# ZUM_Core.net
KiCad netlist of a schematic drawn in Altium Designer
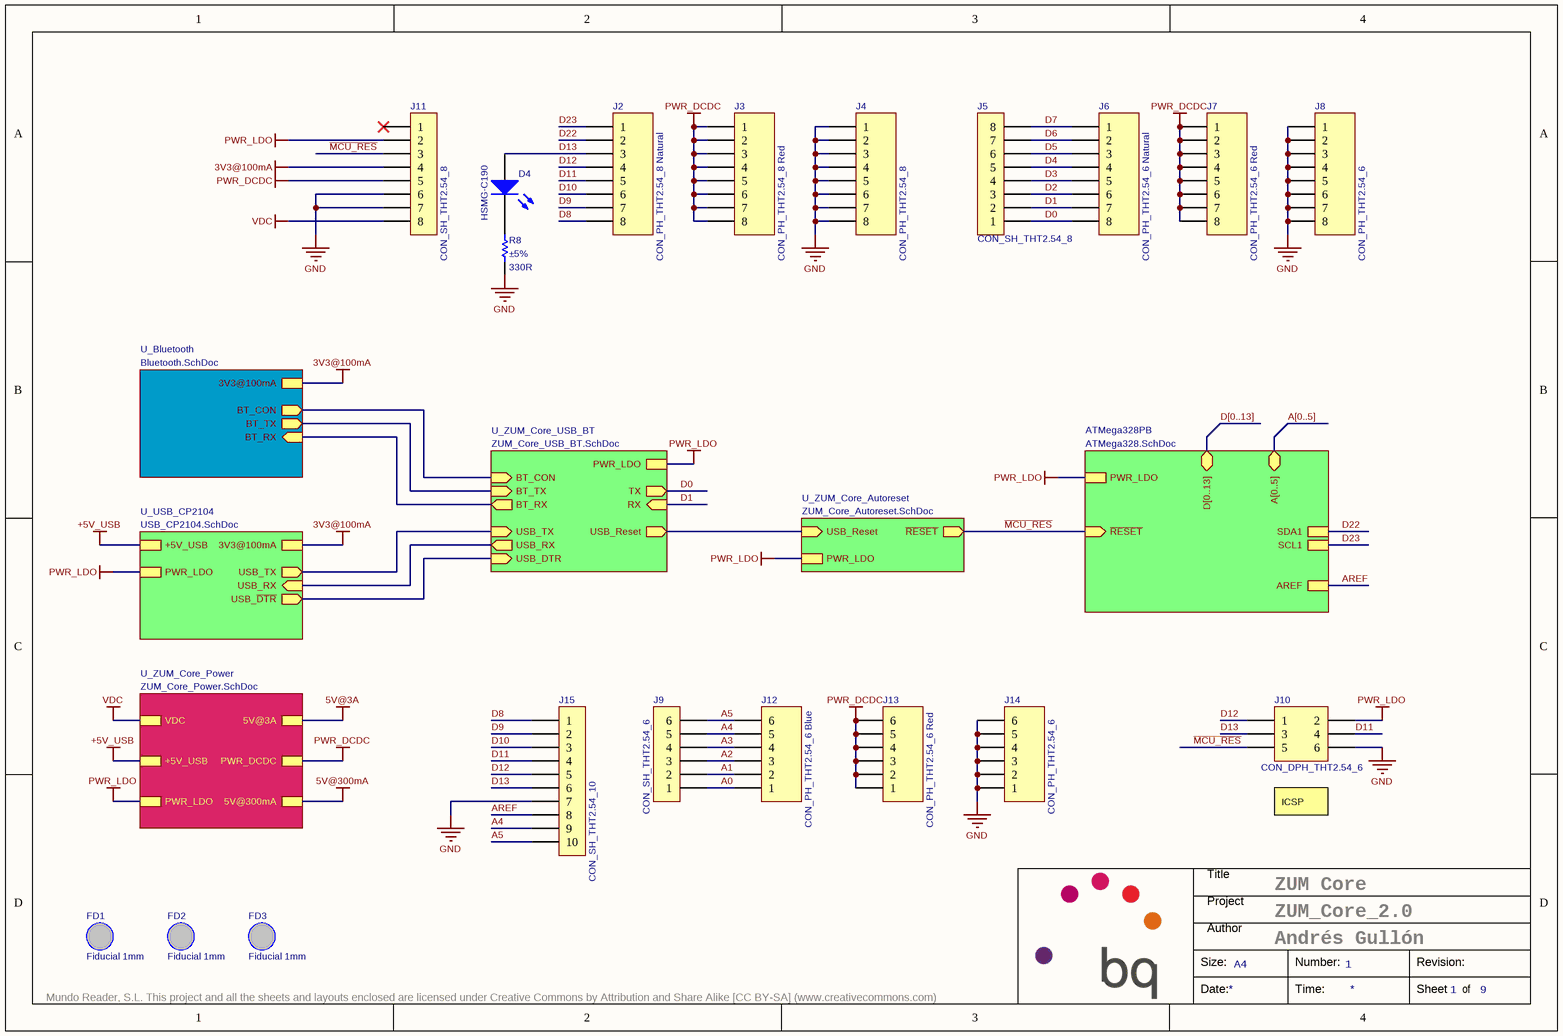
[diagram p0: ZUM_Core.SchDoc]

(export (version "E")
  (design (tool "Eeschema 10.0.6"))
  (components
    (comp (ref "D4")
      (value "HSMG-C190")
      (footprint "LED0603")
      (description "LED")
      (fields (field (name "MANUFACTURER") "Avago Technologies"))
      (libsource (lib "BQ Vault") (part "LED"))
    )
    (comp (ref "FD1")
      (value "Fiducial 1mm")
      (footprint "Fiducial_1mm")
      (description "Fiducial")
      (libsource (lib "BQ Vault") (part "Fiducial"))
    )
    (comp (ref "FD2")
      (value "Fiducial 1mm")
      (footprint "Fiducial_1mm")
      (description "Fiducial")
      (libsource (lib "BQ Vault") (part "Fiducial"))
    )
    (comp (ref "FD3")
      (value "Fiducial 1mm")
      (footprint "Fiducial_1mm")
      (description "Fiducial")
      (libsource (lib "BQ Vault") (part "Fiducial"))
    )
    (comp (ref "J2")
      (value "CON_PH_THT2.54_8 Natural")
      (footprint "1x8 Pin Header 2.54")
      (description "Connector")
      (fields (field (name "MANUFACTURER") "Samtec"))
      (libsource (lib "BQ Vault") (part "CMP-A2144-1"))
    )
    (comp (ref "J3")
      (value "CON_PH_THT2.54_8 Red")
      (footprint "1x8 Pin Header 2.54")
      (description "Connector")
      (fields (field (name "MANUFACTURER") "Samtec"))
      (libsource (lib "BQ Vault") (part "CMP-A2145-1"))
    )
    (comp (ref "J4")
      (value "CON_PH_THT2.54_8")
      (footprint "1x8 Pin Header 2.54")
      (description "Connector")
      (fields (field (name "MANUFACTURER") "Samtec"))
      (libsource (lib "BQ Vault") (part "CMP-A2142-1"))
    )
    (comp (ref "J5")
      (value "CON_SH_THT2.54_8")
      (footprint "1x8 Socket Header THT 2.54mm")
      (description "Connector")
      (fields (field (name "MANUFACTURER") "Samtec"))
      (libsource (lib "BQ Vault") (part "1x8 Socket Header 2.54mm"))
    )
    (comp (ref "J6")
      (value "CON_PH_THT2.54_6 Natural")
      (footprint "1x8 Header 2.54 (3D Mod)")
      (description "Connector")
      (fields (field (name "MANUFACTURER") "Samtec"))
      (libsource (lib "BQ Vault") (part "CMP-00382-1"))
    )
    (comp (ref "J7")
      (value "CON_PH_THT2.54_6 Red")
      (footprint "1x8 Header 2.54 (3D Mod)")
      (description "Connector")
      (fields (field (name "MANUFACTURER") "Samtec"))
      (libsource (lib "BQ Vault") (part "CMP-00380-2"))
    )
    (comp (ref "J8")
      (value "CON_PH_THT2.54_6")
      (footprint "1x8 Header 2.54 (3D Mod)")
      (description "Connector")
      (fields (field (name "MANUFACTURER") "Samtec"))
      (libsource (lib "BQ Vault") (part "1x8 pin Header 2.54mm"))
    )
    (comp (ref "J9")
      (value "CON_SH_THT2.54_6")
      (footprint "1x6 Socket Header THT 2.54mm")
      (description "Connector")
      (fields (field (name "MANUFACTURER") "Samtec"))
      (libsource (lib "BQ Vault") (part "1x6 Socket Header 2.54mm"))
    )
    (comp (ref "J10")
      (value "CON_DPH_THT2.54_6")
      (footprint "2x3 Pin Header 2.54")
      (description "Connector")
      (fields (field (name "MANUFACTURER") "Samtec"))
      (libsource (lib "BQ Vault") (part "CMP-A2163-1"))
    )
    (comp (ref "J11")
      (value "CON_SH_THT2.54_8")
      (footprint "1x8 Socket Header THT 2.54mm")
      (description "Connector")
      (fields (field (name "MANUFACTURER") "Samtec"))
      (libsource (lib "") (part "1x8 Socket Header 2.54mm_1"))
    )
    (comp (ref "J12")
      (value "CON_PH_THT2.54_6 Blue")
      (footprint "1x6 Pin Header 2.54")
      (description "Connector")
      (fields (field (name "MANUFACTURER") "Samtec"))
      (libsource (lib "BQ Vault") (part "CMP-A2139-1"))
    )
    (comp (ref "J13")
      (value "CON_PH_THT2.54_6 Red")
      (footprint "1x6 Pin Header 2.54")
      (description "Connector")
      (fields (field (name "MANUFACTURER") "Samtec"))
      (libsource (lib "BQ Vault") (part "CMP-A2141-1"))
    )
    (comp (ref "J14")
      (value "CON_PH_THT2.54_6")
      (footprint "1x6 Pin Header 2.54")
      (description "Connector")
      (fields (field (name "MANUFACTURER") "Samtec"))
      (libsource (lib "BQ Vault") (part "CMP-A2138-1"))
    )
    (comp (ref "J15")
      (value "CON_SH_THT2.54_10")
      (footprint "1x10 Socket Header THT 2.54mm")
      (description "Connector")
      (fields (field (name "MANUFACTURER") "Samtec"))
      (libsource (lib "BQ Vault") (part "1x10 Socket Header 2.54mm"))
    )
    (comp (ref "R8")
      (value "R0402_330R_0.063W_±5%")
      (footprint "R0402")
      (fields
        (field (name "TOLERANCE") "±5%")
        (field (name "POWER") "0.063W")
        (field (name "RESISTANCE") "330R")
        (field (name "MANUFACTURER") "Vishay")
      )
      (libsource (lib "BQ Vault") (part "CMP-A1762-2"))
    )
  )
  (nets
    (net (code "2") (name "/A0") (class "Default")
      (node (ref "J12") (pin "1") (pinfunction "1_1") (pintype "passive"))
      (node (ref "J9") (pin "1") (pinfunction "1_1") (pintype "passive"))
    )
    (net (code "3") (name "/A1") (class "Default")
      (node (ref "J12") (pin "2") (pinfunction "2_2") (pintype "passive"))
      (node (ref "J9") (pin "2") (pinfunction "2_2") (pintype "passive"))
    )
    (net (code "4") (name "/A2") (class "Default")
      (node (ref "J12") (pin "3") (pinfunction "3_3") (pintype "passive"))
      (node (ref "J9") (pin "3") (pinfunction "3_3") (pintype "passive"))
    )
    (net (code "5") (name "/A3") (class "Default")
      (node (ref "J12") (pin "4") (pinfunction "4_4") (pintype "passive"))
      (node (ref "J9") (pin "4") (pinfunction "4_4") (pintype "passive"))
    )
    (net (code "6") (name "/A4") (class "Default")
      (node (ref "J12") (pin "5") (pinfunction "5_5") (pintype "passive"))
      (node (ref "J15") (pin "9") (pinfunction "9_9") (pintype "passive"))
      (node (ref "J9") (pin "5") (pinfunction "5_5") (pintype "passive"))
    )
    (net (code "7") (name "/A5") (class "Default")
      (node (ref "J12") (pin "6") (pinfunction "6_6") (pintype "passive"))
      (node (ref "J15") (pin "10") (pinfunction "10_10") (pintype "passive"))
      (node (ref "J9") (pin "6") (pinfunction "6_6") (pintype "passive"))
    )
    (net (code "8") (name "/AREF") (class "Default")
      (node (ref "J15") (pin "8") (pinfunction "8_8") (pintype "passive"))
    )
    (net (code "13") (name "/D0") (class "Default")
      (node (ref "J5") (pin "1") (pinfunction "1_1") (pintype "passive"))
      (node (ref "J6") (pin "8") (pinfunction "8_8") (pintype "passive"))
    )
    (net (code "14") (name "/D1") (class "Default")
      (node (ref "J5") (pin "2") (pinfunction "2_2") (pintype "passive"))
      (node (ref "J6") (pin "7") (pinfunction "7_7") (pintype "passive"))
    )
    (net (code "15") (name "/D2") (class "Default")
      (node (ref "J5") (pin "3") (pinfunction "3_3") (pintype "passive"))
      (node (ref "J6") (pin "6") (pinfunction "6_6") (pintype "passive"))
    )
    (net (code "16") (name "/D3") (class "Default")
      (node (ref "J5") (pin "4") (pinfunction "4_4") (pintype "passive"))
      (node (ref "J6") (pin "5") (pinfunction "5_5") (pintype "passive"))
    )
    (net (code "17") (name "/D4") (class "Default")
      (node (ref "J5") (pin "5") (pinfunction "5_5") (pintype "passive"))
      (node (ref "J6") (pin "4") (pinfunction "4_4") (pintype "passive"))
    )
    (net (code "18") (name "/D5") (class "Default")
      (node (ref "J5") (pin "6") (pinfunction "6_6") (pintype "passive"))
      (node (ref "J6") (pin "3") (pinfunction "3_3") (pintype "passive"))
    )
    (net (code "19") (name "/D6") (class "Default")
      (node (ref "J5") (pin "7") (pinfunction "7_7") (pintype "passive"))
      (node (ref "J6") (pin "2") (pinfunction "2_2") (pintype "passive"))
    )
    (net (code "20") (name "/D7") (class "Default")
      (node (ref "J5") (pin "8") (pinfunction "8_8") (pintype "passive"))
      (node (ref "J6") (pin "1") (pinfunction "1_1") (pintype "passive"))
    )
    (net (code "21") (name "/D8") (class "Default")
      (node (ref "J15") (pin "1") (pinfunction "1_1") (pintype "passive"))
      (node (ref "J2") (pin "8") (pinfunction "8_8") (pintype "passive"))
    )
    (net (code "22") (name "/D9") (class "Default")
      (node (ref "J15") (pin "2") (pinfunction "2_2") (pintype "passive"))
      (node (ref "J2") (pin "7") (pinfunction "7_7") (pintype "passive"))
    )
    (net (code "23") (name "/D10") (class "Default")
      (node (ref "J15") (pin "3") (pinfunction "3_3") (pintype "passive"))
      (node (ref "J2") (pin "6") (pinfunction "6_6") (pintype "passive"))
    )
    (net (code "24") (name "/D11") (class "Default")
      (node (ref "J10") (pin "4") (pinfunction "4_4") (pintype "passive"))
      (node (ref "J15") (pin "4") (pinfunction "4_4") (pintype "passive"))
      (node (ref "J2") (pin "5") (pinfunction "5_5") (pintype "passive"))
    )
    (net (code "25") (name "/D12") (class "Default")
      (node (ref "J10") (pin "1") (pinfunction "1_1") (pintype "passive"))
      (node (ref "J15") (pin "5") (pinfunction "5_5") (pintype "passive"))
      (node (ref "J2") (pin "4") (pinfunction "4_4") (pintype "passive"))
    )
    (net (code "26") (name "/D13") (class "Default")
      (node (ref "D4") (pin "A") (pinfunction "A_A") (pintype "passive"))
      (node (ref "J10") (pin "3") (pinfunction "3_3") (pintype "passive"))
      (node (ref "J15") (pin "6") (pinfunction "6_6") (pintype "passive"))
      (node (ref "J2") (pin "3") (pinfunction "3_3") (pintype "passive"))
    )
    (net (code "27") (name "/D22") (class "Default")
      (node (ref "J2") (pin "2") (pinfunction "2_2") (pintype "passive"))
    )
    (net (code "28") (name "/D23") (class "Default")
      (node (ref "J2") (pin "1") (pinfunction "1_1") (pintype "passive"))
    )
    (net (code "34") (name "/~{MCU_RES}") (class "Default")
      (node (ref "J10") (pin "5") (pinfunction "5_5") (pintype "passive"))
      (node (ref "J11") (pin "3") (pinfunction "3_3") (pintype "passive"))
    )
    (net (code "35") (name "3V3@100mA") (class "Default")
      (node (ref "J11") (pin "4") (pinfunction "4_4") (pintype "passive"))
    )
    (net (code "38") (name "GND") (class "Default")
      (node (ref "J10") (pin "6") (pinfunction "6_6") (pintype "passive"))
      (node (ref "J11") (pin "6") (pinfunction "6_6") (pintype "passive"))
      (node (ref "J11") (pin "7") (pinfunction "7_7") (pintype "passive"))
      (node (ref "J14") (pin "1") (pinfunction "1_1") (pintype "passive"))
      (node (ref "J14") (pin "2") (pinfunction "2_2") (pintype "passive"))
      (node (ref "J14") (pin "3") (pinfunction "3_3") (pintype "passive"))
      (node (ref "J14") (pin "4") (pinfunction "4_4") (pintype "passive"))
      (node (ref "J14") (pin "5") (pinfunction "5_5") (pintype "passive"))
      (node (ref "J14") (pin "6") (pinfunction "6_6") (pintype "passive"))
      (node (ref "J15") (pin "7") (pinfunction "7_7") (pintype "passive"))
      (node (ref "J4") (pin "1") (pinfunction "1_1") (pintype "passive"))
      (node (ref "J4") (pin "2") (pinfunction "2_2") (pintype "passive"))
      (node (ref "J4") (pin "3") (pinfunction "3_3") (pintype "passive"))
      (node (ref "J4") (pin "4") (pinfunction "4_4") (pintype "passive"))
      (node (ref "J4") (pin "5") (pinfunction "5_5") (pintype "passive"))
      (node (ref "J4") (pin "6") (pinfunction "6_6") (pintype "passive"))
      (node (ref "J4") (pin "7") (pinfunction "7_7") (pintype "passive"))
      (node (ref "J4") (pin "8") (pinfunction "8_8") (pintype "passive"))
      (node (ref "J8") (pin "1") (pinfunction "1_1") (pintype "passive"))
      (node (ref "J8") (pin "2") (pinfunction "2_2") (pintype "passive"))
      (node (ref "J8") (pin "3") (pinfunction "3_3") (pintype "passive"))
      (node (ref "J8") (pin "4") (pinfunction "4_4") (pintype "passive"))
      (node (ref "J8") (pin "5") (pinfunction "5_5") (pintype "passive"))
      (node (ref "J8") (pin "6") (pinfunction "6_6") (pintype "passive"))
      (node (ref "J8") (pin "7") (pinfunction "7_7") (pintype "passive"))
      (node (ref "J8") (pin "8") (pinfunction "8_8") (pintype "passive"))
      (node (ref "R8") (pin "1") (pinfunction "1_1") (pintype "passive"))
    )
    (net (code "39") (name "Net-(D4-PadK)") (class "Default")
      (node (ref "D4") (pin "K") (pinfunction "K_K") (pintype "passive"))
      (node (ref "R8") (pin "2") (pinfunction "2_2") (pintype "passive"))
    )
    (net (code "40") (name "PWR_DCDC") (class "Default")
      (node (ref "J11") (pin "5") (pinfunction "5_5") (pintype "passive"))
      (node (ref "J13") (pin "1") (pinfunction "1_1") (pintype "passive"))
      (node (ref "J13") (pin "2") (pinfunction "2_2") (pintype "passive"))
      (node (ref "J13") (pin "3") (pinfunction "3_3") (pintype "passive"))
      (node (ref "J13") (pin "4") (pinfunction "4_4") (pintype "passive"))
      (node (ref "J13") (pin "5") (pinfunction "5_5") (pintype "passive"))
      (node (ref "J13") (pin "6") (pinfunction "6_6") (pintype "passive"))
      (node (ref "J3") (pin "1") (pinfunction "1_1") (pintype "passive"))
      (node (ref "J3") (pin "2") (pinfunction "2_2") (pintype "passive"))
      (node (ref "J3") (pin "3") (pinfunction "3_3") (pintype "passive"))
      (node (ref "J3") (pin "4") (pinfunction "4_4") (pintype "passive"))
      (node (ref "J3") (pin "5") (pinfunction "5_5") (pintype "passive"))
      (node (ref "J3") (pin "6") (pinfunction "6_6") (pintype "passive"))
      (node (ref "J3") (pin "7") (pinfunction "7_7") (pintype "passive"))
      (node (ref "J3") (pin "8") (pinfunction "8_8") (pintype "passive"))
      (node (ref "J7") (pin "1") (pinfunction "1_1") (pintype "passive"))
      (node (ref "J7") (pin "2") (pinfunction "2_2") (pintype "passive"))
      (node (ref "J7") (pin "3") (pinfunction "3_3") (pintype "passive"))
      (node (ref "J7") (pin "4") (pinfunction "4_4") (pintype "passive"))
      (node (ref "J7") (pin "5") (pinfunction "5_5") (pintype "passive"))
      (node (ref "J7") (pin "6") (pinfunction "6_6") (pintype "passive"))
      (node (ref "J7") (pin "7") (pinfunction "7_7") (pintype "passive"))
      (node (ref "J7") (pin "8") (pinfunction "8_8") (pintype "passive"))
    )
    (net (code "41") (name "PWR_LDO") (class "Default")
      (node (ref "J10") (pin "2") (pinfunction "2_2") (pintype "passive"))
      (node (ref "J11") (pin "2") (pinfunction "2_2") (pintype "passive"))
    )
    (net (code "42") (name "VDC") (class "Default")
      (node (ref "J11") (pin "8") (pinfunction "8_8") (pintype "passive"))
    )
    (net (code "43") (name "unconnected-(J11-Pad1)") (class "Default")
      (node (ref "J11") (pin "1") (pinfunction "1_1") (pintype "passive+no_connect"))
    )
  )
)
